# Sheet2.net
KiCad netlist of a schematic drawn in Altium Designer
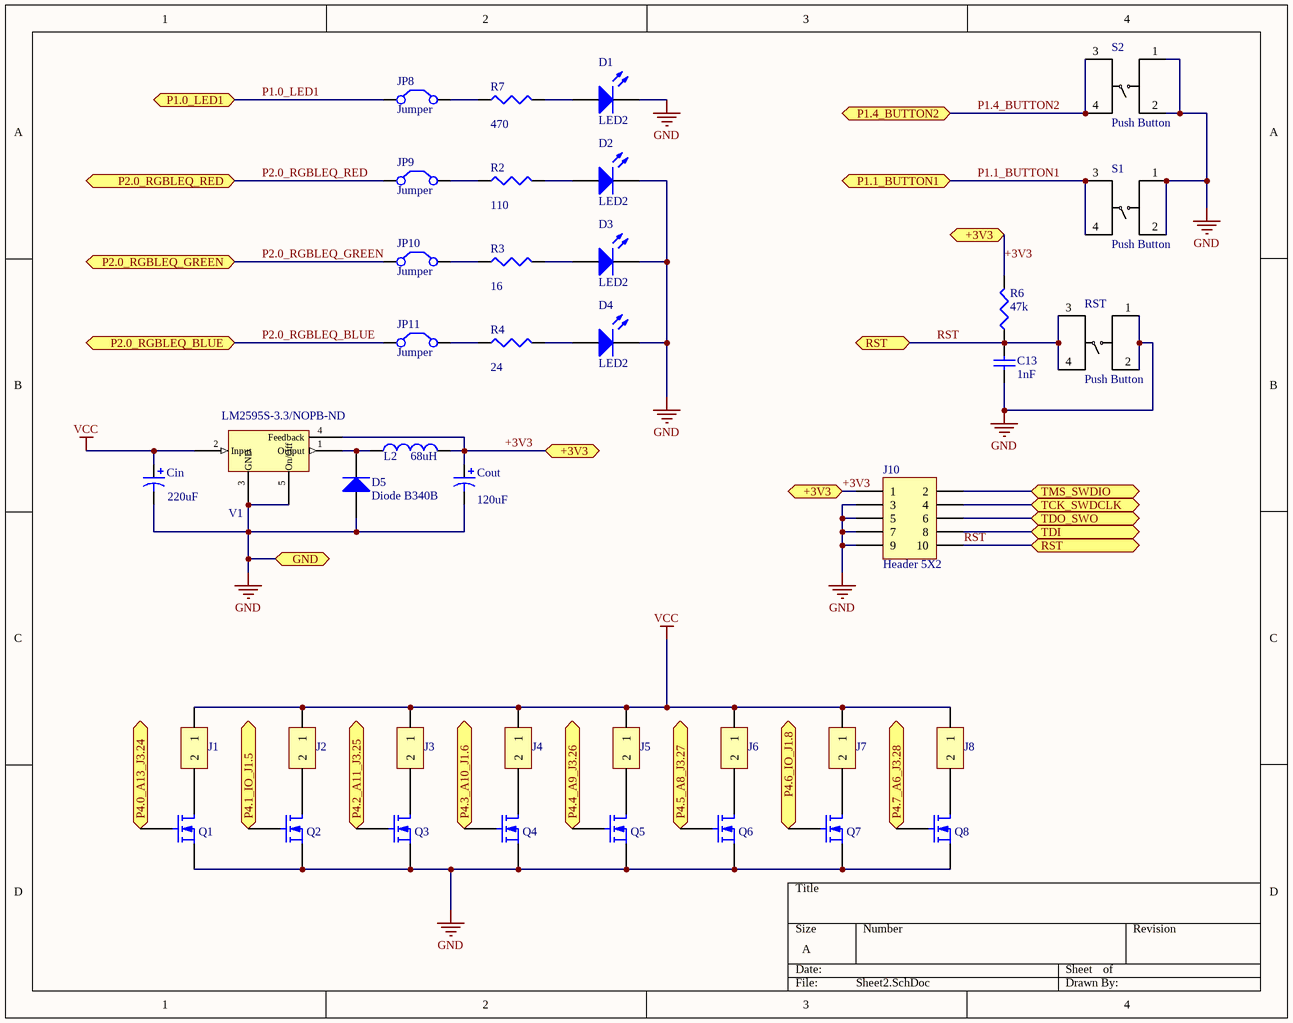
[diagram p0: Sheet2.SchDoc]

(export (version "E")
  (design (tool "Eeschema 10.0.6"))
  (components
    (comp (ref "C13")
      (value "1nF")
      (footprint "0402")
      (description "Capacitor (Semiconductor SIM Model)")
      (fields (field (name "Comment") "Cap Semi") (field (name "PUBLISHER") "Altium Limited"))
      (libsource (lib "Miscellaneous Devices") (part "Cap Semi"))
    )
    (comp (ref "Cin")
      (value "220uF")
      (footprint "C0805")
      (description "Polarized Capacitor (Surface Mount)")
      (fields (field (name "Comment") "Cap Pol3") (field (name "PUBLISHER") "Altium Limited"))
      (libsource (lib "Miscellaneous Devices") (part "Cap Pol3"))
    )
    (comp (ref "Cout")
      (value "120uF")
      (footprint "C0805")
      (description "Polarized Capacitor (Surface Mount)")
      (fields (field (name "Comment") "Cap Pol3") (field (name "PUBLISHER") "Altium Limited"))
      (libsource (lib "Miscellaneous Devices") (part "Cap Pol3"))
    )
    (comp (ref "D1")
      (value "LED2")
      (footprint "3.2X1.6X1.1")
      (description "Typical RED, GREEN, YELLOW, AMBER GaAs LED")
      (fields (field (name "PUBLISHER") "Altium Limited"))
      (libsource (lib "Miscellaneous Devices") (part "LED2"))
    )
    (comp (ref "D2")
      (value "LED2")
      (footprint "3.2X1.6X1.1")
      (description "Typical RED, GREEN, YELLOW, AMBER GaAs LED")
      (fields (field (name "PUBLISHER") "Altium Limited"))
      (libsource (lib "Miscellaneous Devices") (part "LED2"))
    )
    (comp (ref "D3")
      (value "LED2")
      (footprint "3.2X1.6X1.1")
      (description "Typical RED, GREEN, YELLOW, AMBER GaAs LED")
      (fields (field (name "PUBLISHER") "Altium Limited"))
      (libsource (lib "Miscellaneous Devices") (part "LED2"))
    )
    (comp (ref "D4")
      (value "LED2")
      (footprint "3.2X1.6X1.1")
      (description "Typical RED, GREEN, YELLOW, AMBER GaAs LED")
      (fields (field (name "PUBLISHER") "Altium Limited"))
      (libsource (lib "Miscellaneous Devices") (part "LED2"))
    )
    (comp (ref "D5")
      (value "Diode B340B")
      (footprint "SMB")
      (description "Default Diode")
      (fields (field (name "PUBLISHER") "Altium Limited"))
      (libsource (lib "Miscellaneous Devices") (part "Diode"))
    )
    (comp (ref "J1")
      (value "MOLEX 2CKT Header")
      (footprint "MOLEX 2CKT Header")
      (libsource (lib "actuatorBoard") (part "MOLEX 2CKT Header"))
    )
    (comp (ref "J2")
      (value "MOLEX 2CKT Header")
      (footprint "MOLEX 2CKT Header")
      (libsource (lib "actuatorBoard") (part "MOLEX 2CKT Header"))
    )
    (comp (ref "J3")
      (value "MOLEX 2CKT Header")
      (footprint "MOLEX 2CKT Header")
      (libsource (lib "actuatorBoard") (part "MOLEX 2CKT Header"))
    )
    (comp (ref "J4")
      (value "MOLEX 2CKT Header")
      (footprint "MOLEX 2CKT Header")
      (libsource (lib "actuatorBoard") (part "MOLEX 2CKT Header"))
    )
    (comp (ref "J5")
      (value "MOLEX 2CKT Header")
      (footprint "MOLEX 2CKT Header")
      (libsource (lib "actuatorBoard") (part "MOLEX 2CKT Header"))
    )
    (comp (ref "J6")
      (value "MOLEX 2CKT Header")
      (footprint "MOLEX 2CKT Header")
      (libsource (lib "actuatorBoard") (part "MOLEX 2CKT Header"))
    )
    (comp (ref "J7")
      (value "MOLEX 2CKT Header")
      (footprint "MOLEX 2CKT Header")
      (libsource (lib "actuatorBoard") (part "MOLEX 2CKT Header"))
    )
    (comp (ref "J8")
      (value "MOLEX 2CKT Header")
      (footprint "MOLEX 2CKT Header")
      (libsource (lib "actuatorBoard") (part "MOLEX 2CKT Header"))
    )
    (comp (ref "J10")
      (value "Header 5X2")
      (footprint "HDR2X5")
      (description "Header, 5-Pin, Dual row")
      (fields (field (name "PUBLISHER") "Altium Limited"))
      (libsource (lib "Miscellaneous Connectors") (part "Header 5X2"))
    )
    (comp (ref "JP8")
      (value "Jumper")
      (footprint "HDR1X2")
      (description "Jumper Wire")
      (fields (field (name "PUBLISHER") "Altium Limited"))
      (libsource (lib "Miscellaneous Devices") (part "Jumper"))
    )
    (comp (ref "JP9")
      (value "Jumper")
      (footprint "HDR1X2")
      (description "Jumper Wire")
      (fields (field (name "PUBLISHER") "Altium Limited"))
      (libsource (lib "Miscellaneous Devices") (part "Jumper"))
    )
    (comp (ref "JP10")
      (value "Jumper")
      (footprint "HDR1X2")
      (description "Jumper Wire")
      (fields (field (name "PUBLISHER") "Altium Limited"))
      (libsource (lib "Miscellaneous Devices") (part "Jumper"))
    )
    (comp (ref "JP11")
      (value "Jumper")
      (footprint "HDR1X2")
      (description "Jumper Wire")
      (fields (field (name "PUBLISHER") "Altium Limited"))
      (libsource (lib "Miscellaneous Devices") (part "Jumper"))
    )
    (comp (ref "L2")
      (value "68uH")
      (footprint "0402-A")
      (description "Inductor")
      (fields (field (name "PUBLISHER") "Altium Limited"))
      (libsource (lib "Miscellaneous Devices") (part "Inductor"))
    )
    (comp (ref "Q1")
      (value "MOSFET-N")
      (footprint "SiUD41ED")
      (libsource (lib "actuatorBoard") (part "SiUD41ED"))
    )
    (comp (ref "Q2")
      (value "MOSFET-N")
      (footprint "SiUD41ED")
      (libsource (lib "actuatorBoard") (part "SiUD41ED"))
    )
    (comp (ref "Q3")
      (value "MOSFET-N")
      (footprint "SiUD41ED")
      (libsource (lib "actuatorBoard") (part "SiUD41ED"))
    )
    (comp (ref "Q4")
      (value "MOSFET-N")
      (footprint "SiUD41ED")
      (libsource (lib "actuatorBoard") (part "SiUD41ED"))
    )
    (comp (ref "Q5")
      (value "MOSFET-N")
      (footprint "SiUD41ED")
      (libsource (lib "actuatorBoard") (part "SiUD41ED"))
    )
    (comp (ref "Q6")
      (value "MOSFET-N")
      (footprint "SiUD41ED")
      (libsource (lib "actuatorBoard") (part "SiUD41ED"))
    )
    (comp (ref "Q7")
      (value "MOSFET-N")
      (footprint "SiUD41ED")
      (libsource (lib "actuatorBoard") (part "SiUD41ED"))
    )
    (comp (ref "Q8")
      (value "MOSFET-N")
      (footprint "SiUD41ED")
      (libsource (lib "actuatorBoard") (part "SiUD41ED"))
    )
    (comp (ref "R2")
      (value "110")
      (footprint "J1-0603")
      (description "Resistor")
      (fields (field (name "Comment") "Res3") (field (name "PUBLISHER") "Altium Limited"))
      (libsource (lib "Miscellaneous Devices") (part "Res3"))
    )
    (comp (ref "R3")
      (value "16")
      (footprint "J1-0603")
      (description "Resistor")
      (fields (field (name "Comment") "Res3") (field (name "PUBLISHER") "Altium Limited"))
      (libsource (lib "Miscellaneous Devices") (part "Res3"))
    )
    (comp (ref "R4")
      (value "24")
      (footprint "J1-0603")
      (description "Resistor")
      (fields (field (name "Comment") "Res3") (field (name "PUBLISHER") "Altium Limited"))
      (libsource (lib "Miscellaneous Devices") (part "Res3"))
    )
    (comp (ref "R6")
      (value "47k")
      (footprint "J1-0603")
      (description "Resistor")
      (fields (field (name "Comment") "Res3") (field (name "PUBLISHER") "Altium Limited"))
      (libsource (lib "Miscellaneous Devices") (part "Res3"))
    )
    (comp (ref "R7")
      (value "470")
      (footprint "J1-0603")
      (description "Resistor")
      (fields (field (name "Comment") "Res3") (field (name "PUBLISHER") "Altium Limited"))
      (libsource (lib "Miscellaneous Devices") (part "Res3"))
    )
    (comp (ref "RST")
      (value "Push Button")
      (footprint "Push Button")
      (libsource (lib "actuatorBoard") (part "Push Button"))
    )
    (comp (ref "S1")
      (value "Push Button")
      (footprint "Push Button")
      (libsource (lib "actuatorBoard") (part "Push Button"))
    )
    (comp (ref "S2")
      (value "Push Button")
      (footprint "Push Button")
      (libsource (lib "actuatorBoard") (part "Push Button"))
    )
    (comp (ref "V1")
      (value "LM2595S-3.3/NOPB-ND")
      (footprint "LM2595S-3.3/NOPB-ND")
      (libsource (lib "actuatorBoard") (part "LM2595S-3.3/NOPB-ND"))
    )
  )
  (nets
    (net (code "1") (name "/+3V3") (class "Default")
      (node (ref "Cout") (pin "1") (pinfunction "1_1") (pintype "passive"))
      (node (ref "J10") (pin "1") (pinfunction "1_1") (pintype "passive"))
      (node (ref "L2") (pin "2") (pinfunction "2_2") (pintype "passive"))
      (node (ref "R6") (pin "2") (pinfunction "2_2") (pintype "passive"))
      (node (ref "V1") (pin "4") (pinfunction "Feedback_4") (pintype "passive"))
    )
    (net (code "2") (name "/P1.0_LED1") (class "Default")
      (node (ref "JP8") (pin "1") (pinfunction "C1_1") (pintype "passive"))
    )
    (net (code "3") (name "/P1.1_BUTTON1") (class "Default")
      (node (ref "S1") (pin "3") (pinfunction "3_3") (pintype "passive"))
      (node (ref "S1") (pin "4") (pinfunction "4_4") (pintype "passive"))
    )
    (net (code "4") (name "/P1.4_BUTTON2") (class "Default")
      (node (ref "S2") (pin "3") (pinfunction "3_3") (pintype "passive"))
      (node (ref "S2") (pin "4") (pinfunction "4_4") (pintype "passive"))
    )
    (net (code "5") (name "/P2.0_RGBLEQ_BLUE") (class "Default")
      (node (ref "JP11") (pin "1") (pinfunction "C1_1") (pintype "passive"))
    )
    (net (code "6") (name "/P2.0_RGBLEQ_GREEN") (class "Default")
      (node (ref "JP10") (pin "1") (pinfunction "C1_1") (pintype "passive"))
    )
    (net (code "7") (name "/P2.0_RGBLEQ_RED") (class "Default")
      (node (ref "JP9") (pin "1") (pinfunction "C1_1") (pintype "passive"))
    )
    (net (code "8") (name "/P4.0_A13_J3.24") (class "Default")
      (node (ref "Q1") (pin "1") (pinfunction "1_1") (pintype "passive"))
    )
    (net (code "9") (name "/P4.1_IO_J1.5") (class "Default")
      (node (ref "Q2") (pin "1") (pinfunction "1_1") (pintype "passive"))
    )
    (net (code "10") (name "/P4.2_A11_J3.25") (class "Default")
      (node (ref "Q3") (pin "1") (pinfunction "1_1") (pintype "passive"))
    )
    (net (code "11") (name "/P4.3_A10_J1.6") (class "Default")
      (node (ref "Q4") (pin "1") (pinfunction "1_1") (pintype "passive"))
    )
    (net (code "12") (name "/P4.4_A9_J3.26") (class "Default")
      (node (ref "Q5") (pin "1") (pinfunction "1_1") (pintype "passive"))
    )
    (net (code "13") (name "/P4.5_A8_J3.27") (class "Default")
      (node (ref "Q6") (pin "1") (pinfunction "1_1") (pintype "passive"))
    )
    (net (code "14") (name "/P4.6_IO_J1.8") (class "Default")
      (node (ref "Q7") (pin "1") (pinfunction "1_1") (pintype "passive"))
    )
    (net (code "15") (name "/P4.7_A6_J3.28") (class "Default")
      (node (ref "Q8") (pin "1") (pinfunction "1_1") (pintype "passive"))
    )
    (net (code "16") (name "/RST") (class "Default")
      (node (ref "C13") (pin "2") (pinfunction "2_2") (pintype "passive"))
      (node (ref "J10") (pin "10") (pinfunction "10_10") (pintype "passive"))
      (node (ref "R6") (pin "1") (pinfunction "1_1") (pintype "passive"))
      (node (ref "RST") (pin "3") (pinfunction "3_3") (pintype "passive"))
      (node (ref "RST") (pin "4") (pinfunction "4_4") (pintype "passive"))
    )
    (net (code "17") (name "/TCK_SWDCLK") (class "Default")
      (node (ref "J10") (pin "4") (pinfunction "4_4") (pintype "passive"))
    )
    (net (code "18") (name "/TDI") (class "Default")
      (node (ref "J10") (pin "8") (pinfunction "8_8") (pintype "passive"))
    )
    (net (code "19") (name "/TDO_SWO") (class "Default")
      (node (ref "J10") (pin "6") (pinfunction "6_6") (pintype "passive"))
    )
    (net (code "20") (name "/TMS_SWDIO") (class "Default")
      (node (ref "J10") (pin "2") (pinfunction "2_2") (pintype "passive"))
    )
    (net (code "21") (name "GND") (class "Default")
      (node (ref "C13") (pin "1") (pinfunction "1_1") (pintype "passive"))
      (node (ref "Cin") (pin "2") (pinfunction "2_2") (pintype "passive"))
      (node (ref "Cout") (pin "2") (pinfunction "2_2") (pintype "passive"))
      (node (ref "D1") (pin "2") (pinfunction "K_2") (pintype "passive"))
      (node (ref "D2") (pin "2") (pinfunction "K_2") (pintype "passive"))
      (node (ref "D3") (pin "2") (pinfunction "K_2") (pintype "passive"))
      (node (ref "D4") (pin "2") (pinfunction "K_2") (pintype "passive"))
      (node (ref "D5") (pin "1") (pinfunction "A_1") (pintype "passive"))
      (node (ref "J10") (pin "3") (pinfunction "3_3") (pintype "passive"))
      (node (ref "J10") (pin "5") (pinfunction "5_5") (pintype "passive"))
      (node (ref "J10") (pin "7") (pinfunction "7_7") (pintype "passive"))
      (node (ref "J10") (pin "9") (pinfunction "9_9") (pintype "passive"))
      (node (ref "Q1") (pin "2") (pinfunction "2_2") (pintype "passive"))
      (node (ref "Q2") (pin "2") (pinfunction "2_2") (pintype "passive"))
      (node (ref "Q3") (pin "2") (pinfunction "2_2") (pintype "passive"))
      (node (ref "Q4") (pin "2") (pinfunction "2_2") (pintype "passive"))
      (node (ref "Q5") (pin "2") (pinfunction "2_2") (pintype "passive"))
      (node (ref "Q6") (pin "2") (pinfunction "2_2") (pintype "passive"))
      (node (ref "Q7") (pin "2") (pinfunction "2_2") (pintype "passive"))
      (node (ref "Q8") (pin "2") (pinfunction "2_2") (pintype "passive"))
      (node (ref "RST") (pin "1") (pinfunction "1_1") (pintype "passive"))
      (node (ref "RST") (pin "2") (pinfunction "2_2") (pintype "passive"))
      (node (ref "S1") (pin "1") (pinfunction "1_1") (pintype "passive"))
      (node (ref "S1") (pin "2") (pinfunction "2_2") (pintype "passive"))
      (node (ref "S2") (pin "1") (pinfunction "1_1") (pintype "passive"))
      (node (ref "S2") (pin "2") (pinfunction "2_2") (pintype "passive"))
      (node (ref "V1") (pin "3") (pinfunction "GND_3") (pintype "passive"))
      (node (ref "V1") (pin "5") (pinfunction "On/Off_5") (pintype "passive"))
    )
    (net (code "22") (name "Net-(D1-A)") (class "Default")
      (node (ref "D1") (pin "1") (pinfunction "A_1") (pintype "passive"))
      (node (ref "R7") (pin "2") (pinfunction "2_2") (pintype "passive"))
    )
    (net (code "23") (name "Net-(D2-A)") (class "Default")
      (node (ref "D2") (pin "1") (pinfunction "A_1") (pintype "passive"))
      (node (ref "R2") (pin "2") (pinfunction "2_2") (pintype "passive"))
    )
    (net (code "24") (name "Net-(D3-A)") (class "Default")
      (node (ref "D3") (pin "1") (pinfunction "A_1") (pintype "passive"))
      (node (ref "R3") (pin "2") (pinfunction "2_2") (pintype "passive"))
    )
    (net (code "25") (name "Net-(D4-A)") (class "Default")
      (node (ref "D4") (pin "1") (pinfunction "A_1") (pintype "passive"))
      (node (ref "R4") (pin "2") (pinfunction "2_2") (pintype "passive"))
    )
    (net (code "26") (name "Net-(D5-K)") (class "Default")
      (node (ref "D5") (pin "2") (pinfunction "K_2") (pintype "passive"))
      (node (ref "L2") (pin "1") (pinfunction "1_1") (pintype "passive"))
      (node (ref "V1") (pin "1") (pinfunction "Output_1") (pintype "output"))
    )
    (net (code "27") (name "Net-(J1-Pad2)") (class "Default")
      (node (ref "J1") (pin "2") (pinfunction "2_2") (pintype "power_in"))
      (node (ref "Q1") (pin "3") (pinfunction "3_3") (pintype "passive"))
    )
    (net (code "28") (name "Net-(J2-Pad2)") (class "Default")
      (node (ref "J2") (pin "2") (pinfunction "2_2") (pintype "power_in"))
      (node (ref "Q2") (pin "3") (pinfunction "3_3") (pintype "passive"))
    )
    (net (code "29") (name "Net-(J3-Pad2)") (class "Default")
      (node (ref "J3") (pin "2") (pinfunction "2_2") (pintype "power_in"))
      (node (ref "Q3") (pin "3") (pinfunction "3_3") (pintype "passive"))
    )
    (net (code "30") (name "Net-(J4-Pad2)") (class "Default")
      (node (ref "J4") (pin "2") (pinfunction "2_2") (pintype "power_in"))
      (node (ref "Q4") (pin "3") (pinfunction "3_3") (pintype "passive"))
    )
    (net (code "31") (name "Net-(J5-Pad2)") (class "Default")
      (node (ref "J5") (pin "2") (pinfunction "2_2") (pintype "power_in"))
      (node (ref "Q5") (pin "3") (pinfunction "3_3") (pintype "passive"))
    )
    (net (code "32") (name "Net-(J6-Pad2)") (class "Default")
      (node (ref "J6") (pin "2") (pinfunction "2_2") (pintype "power_in"))
      (node (ref "Q6") (pin "3") (pinfunction "3_3") (pintype "passive"))
    )
    (net (code "33") (name "Net-(J7-Pad2)") (class "Default")
      (node (ref "J7") (pin "2") (pinfunction "2_2") (pintype "power_in"))
      (node (ref "Q7") (pin "3") (pinfunction "3_3") (pintype "passive"))
    )
    (net (code "34") (name "Net-(J8-Pad2)") (class "Default")
      (node (ref "J8") (pin "2") (pinfunction "2_2") (pintype "power_in"))
      (node (ref "Q8") (pin "3") (pinfunction "3_3") (pintype "passive"))
    )
    (net (code "35") (name "Net-(JP8-C2)") (class "Default")
      (node (ref "JP8") (pin "2") (pinfunction "C2_2") (pintype "passive"))
      (node (ref "R7") (pin "1") (pinfunction "1_1") (pintype "passive"))
    )
    (net (code "36") (name "Net-(JP9-C2)") (class "Default")
      (node (ref "JP9") (pin "2") (pinfunction "C2_2") (pintype "passive"))
      (node (ref "R2") (pin "1") (pinfunction "1_1") (pintype "passive"))
    )
    (net (code "37") (name "Net-(JP10-C2)") (class "Default")
      (node (ref "JP10") (pin "2") (pinfunction "C2_2") (pintype "passive"))
      (node (ref "R3") (pin "1") (pinfunction "1_1") (pintype "passive"))
    )
    (net (code "38") (name "Net-(JP11-C2)") (class "Default")
      (node (ref "JP11") (pin "2") (pinfunction "C2_2") (pintype "passive"))
      (node (ref "R4") (pin "1") (pinfunction "1_1") (pintype "passive"))
    )
    (net (code "39") (name "VCC") (class "Default")
      (node (ref "Cin") (pin "1") (pinfunction "1_1") (pintype "passive"))
      (node (ref "J1") (pin "1") (pinfunction "1_1") (pintype "power_in"))
      (node (ref "J2") (pin "1") (pinfunction "1_1") (pintype "power_in"))
      (node (ref "J3") (pin "1") (pinfunction "1_1") (pintype "power_in"))
      (node (ref "J4") (pin "1") (pinfunction "1_1") (pintype "power_in"))
      (node (ref "J5") (pin "1") (pinfunction "1_1") (pintype "power_in"))
      (node (ref "J6") (pin "1") (pinfunction "1_1") (pintype "power_in"))
      (node (ref "J7") (pin "1") (pinfunction "1_1") (pintype "power_in"))
      (node (ref "J8") (pin "1") (pinfunction "1_1") (pintype "power_in"))
      (node (ref "V1") (pin "2") (pinfunction "Input_2") (pintype "input"))
    )
  )
)
